# 2_interface.net
KiCad netlist of a schematic drawn in Altium Designer
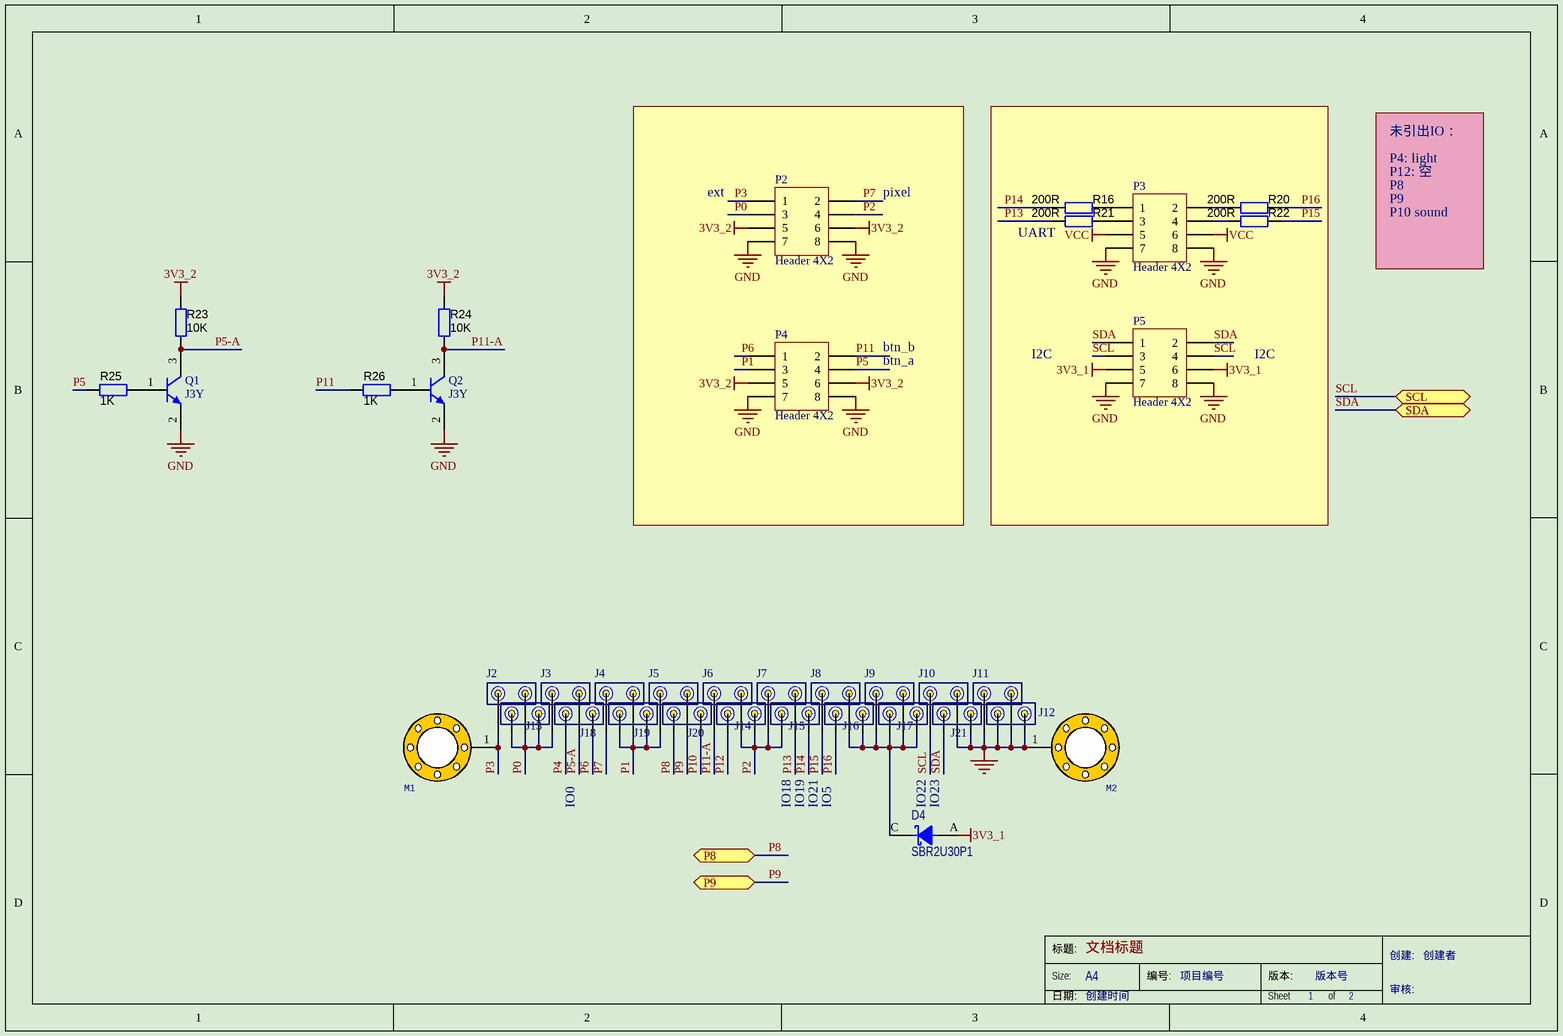
[diagram p0: 2.interface.SchDoc]

(export (version "E")
  (design (tool "Eeschema 10.0.6"))
  (components
    (comp (ref "D4")
      (value "SBR2U30P1")
      (footprint "POWERDI123")
      (fields (field (name "PARTNUMBER") "?") (field (name "PUBLISHER") "Altium Limited"))
      (libsource (lib "03.常用器件") (part "Diode_Schottky"))
    )
    (comp (ref "J2") (value "~") (footprint "顶针座子（2.54MM）") (libsource (lib "Schlib1") (part "pogopin")))
    (comp (ref "J3") (value "~") (footprint "顶针座子（2.54MM）") (libsource (lib "Schlib1") (part "pogopin")))
    (comp (ref "J4") (value "~") (footprint "顶针座子（2.54MM）") (libsource (lib "Schlib1") (part "pogopin")))
    (comp (ref "J5") (value "~") (footprint "顶针座子（2.54MM）") (libsource (lib "Schlib1") (part "pogopin")))
    (comp (ref "J6") (value "~") (footprint "顶针座子（2.54MM）") (libsource (lib "Schlib1") (part "pogopin")))
    (comp (ref "J7") (value "~") (footprint "顶针座子（2.54MM）") (libsource (lib "Schlib1") (part "pogopin")))
    (comp (ref "J8") (value "~") (footprint "顶针座子（2.54MM）") (libsource (lib "Schlib1") (part "pogopin")))
    (comp (ref "J9") (value "~") (footprint "顶针座子（2.54MM）") (libsource (lib "Schlib1") (part "pogopin")))
    (comp (ref "J10") (value "~") (footprint "顶针座子（2.54MM）") (libsource (lib "Schlib1") (part "pogopin")))
    (comp (ref "J11") (value "~") (footprint "顶针座子（2.54MM）") (libsource (lib "Schlib1") (part "pogopin")))
    (comp (ref "J12") (value "~") (footprint "顶针座子（2.54MM）") (libsource (lib "Schlib1") (part "pogopin_32")))
    (comp (ref "J13") (value "~") (footprint "顶针座子（2.54MM）") (libsource (lib "Schlib1") (part "pogopin_32")))
    (comp (ref "J14") (value "~") (footprint "顶针座子（2.54MM）") (libsource (lib "Schlib1") (part "pogopin_32")))
    (comp (ref "J15") (value "~") (footprint "顶针座子（2.54MM）") (libsource (lib "Schlib1") (part "pogopin_32")))
    (comp (ref "J16") (value "~") (footprint "顶针座子（2.54MM）") (libsource (lib "Schlib1") (part "pogopin_32")))
    (comp (ref "J17") (value "~") (footprint "顶针座子（2.54MM）") (libsource (lib "Schlib1") (part "pogopin_32")))
    (comp (ref "J18") (value "~") (footprint "顶针座子（2.54MM）") (libsource (lib "Schlib1") (part "pogopin_32")))
    (comp (ref "J19") (value "~") (footprint "顶针座子（2.54MM）") (libsource (lib "Schlib1") (part "pogopin_32")))
    (comp (ref "J20") (value "~") (footprint "顶针座子（2.54MM）") (libsource (lib "Schlib1") (part "pogopin_32")))
    (comp (ref "J21") (value "~") (footprint "顶针座子（2.54MM）") (libsource (lib "Schlib1") (part "pogopin_32")))
    (comp (ref "M1") (value "~") (footprint "3MM螺丝孔") (libsource (lib "labplus-connector") (part "screw")))
    (comp (ref "M2") (value "~") (footprint "3MM螺丝孔") (libsource (lib "labplus-connector") (part "screw")))
    (comp (ref "P2")
      (value "Header 4X2")
      (footprint "HDR2X4")
      (description "Header, 4-Pin, Dual row")
      (fields (field (name "PUBLISHER") "Altium Limited"))
      (libsource (lib "Miscellaneous Connectors") (part "Header 4X2"))
    )
    (comp (ref "P3")
      (value "Header 4X2")
      (footprint "HDR2X4")
      (description "Header, 4-Pin, Dual row")
      (fields (field (name "PUBLISHER") "Altium Limited"))
      (libsource (lib "Miscellaneous Connectors") (part "Header 4X2"))
    )
    (comp (ref "P4")
      (value "Header 4X2")
      (footprint "HDR2X4")
      (description "Header, 4-Pin, Dual row")
      (fields (field (name "PUBLISHER") "Altium Limited"))
      (libsource (lib "Miscellaneous Connectors") (part "Header 4X2"))
    )
    (comp (ref "P5")
      (value "Header 4X2")
      (footprint "HDR2X4")
      (description "Header, 4-Pin, Dual row")
      (fields (field (name "PUBLISHER") "Altium Limited"))
      (libsource (lib "Miscellaneous Connectors") (part "Header 4X2"))
    )
    (comp (ref "Q1")
      (value "J3Y")
      (footprint "DFN 3L")
      (description "NPN General Purpose Amplifier")
      (fields (field (name "PUBLISHER") "Altium Limited"))
      (libsource (lib "Schlib1") (part "2N3904"))
    )
    (comp (ref "Q2")
      (value "J3Y")
      (footprint "DFN 3L")
      (description "NPN General Purpose Amplifier")
      (fields (field (name "PUBLISHER") "Altium Limited"))
      (libsource (lib "Schlib1") (part "2N3904"))
    )
    (comp (ref "R16")
      (value "200R")
      (footprint "0402")
      (description "RES, 1.0k ohm, 5%, 0.1W, 0603")
      (fields
        (field (name "PARTNUMBER") "RC0603JR-071KL")
        (field (name "MANUFACTURER") "Yageo America")
        (field (name "PUBLISHER") "Texas Instruments")
      )
      (libsource (lib "") (part "RES1_2"))
    )
    (comp (ref "R20")
      (value "200R")
      (footprint "0402")
      (description "RES, 1.0k ohm, 5%, 0.1W, 0603")
      (fields
        (field (name "PARTNUMBER") "RC0603JR-071KL")
        (field (name "MANUFACTURER") "Yageo America")
        (field (name "PUBLISHER") "Texas Instruments")
      )
      (libsource (lib "") (part "RES1_2"))
    )
    (comp (ref "R21")
      (value "200R")
      (footprint "0402")
      (description "RES, 1.0k ohm, 5%, 0.1W, 0603")
      (fields
        (field (name "PARTNUMBER") "RC0603JR-071KL")
        (field (name "MANUFACTURER") "Yageo America")
        (field (name "PUBLISHER") "Texas Instruments")
      )
      (libsource (lib "") (part "RES1_2"))
    )
    (comp (ref "R22")
      (value "200R")
      (footprint "0402")
      (description "RES, 1.0k ohm, 5%, 0.1W, 0603")
      (fields
        (field (name "PARTNUMBER") "RC0603JR-071KL")
        (field (name "MANUFACTURER") "Yageo America")
        (field (name "PUBLISHER") "Texas Instruments")
      )
      (libsource (lib "") (part "RES1_2"))
    )
    (comp (ref "R23")
      (value "10K")
      (footprint "0402")
      (description "RES, 1.0k ohm, 5%, 0.1W, 0603")
      (fields
        (field (name "PARTNUMBER") "RC0603JR-071KL")
        (field (name "MANUFACTURER") "Yageo America")
        (field (name "PUBLISHER") "Texas Instruments")
      )
      (libsource (lib "03.常用器件") (part "RES1"))
    )
    (comp (ref "R24")
      (value "10K")
      (footprint "0402")
      (description "RES, 1.0k ohm, 5%, 0.1W, 0603")
      (fields
        (field (name "PARTNUMBER") "RC0603JR-071KL")
        (field (name "MANUFACTURER") "Yageo America")
        (field (name "PUBLISHER") "Texas Instruments")
      )
      (libsource (lib "03.常用器件") (part "RES1"))
    )
    (comp (ref "R25")
      (value "1K")
      (footprint "0402")
      (description "RES, 1.0k ohm, 5%, 0.1W, 0603")
      (fields
        (field (name "PARTNUMBER") "RC0603JR-071KL")
        (field (name "MANUFACTURER") "Yageo America")
        (field (name "PUBLISHER") "Texas Instruments")
      )
      (libsource (lib "") (part "RES1_1"))
    )
    (comp (ref "R26")
      (value "1K")
      (footprint "0402")
      (description "RES, 1.0k ohm, 5%, 0.1W, 0603")
      (fields
        (field (name "PARTNUMBER") "RC0603JR-071KL")
        (field (name "MANUFACTURER") "Yageo America")
        (field (name "PUBLISHER") "Texas Instruments")
      )
      (libsource (lib "") (part "RES1_1"))
    )
  )
  (nets
    (net (code "1") (name "/P0") (class "Default")
      (node (ref "J13") (pin "1") (pinfunction "1_1") (pintype "passive"))
      (node (ref "J13") (pin "2") (pinfunction "2_2") (pintype "passive"))
      (node (ref "J2") (pin "2") (pinfunction "2_2") (pintype "passive"))
      (node (ref "J3") (pin "1") (pinfunction "1_1") (pintype "passive"))
      (node (ref "P2") (pin "3") (pinfunction "3_3") (pintype "passive"))
    )
    (net (code "2") (name "/P1") (class "Default")
      (node (ref "J19") (pin "1") (pinfunction "1_1") (pintype "passive"))
      (node (ref "J19") (pin "2") (pinfunction "2_2") (pintype "passive"))
      (node (ref "J4") (pin "2") (pinfunction "2_2") (pintype "passive"))
      (node (ref "J5") (pin "1") (pinfunction "1_1") (pintype "passive"))
      (node (ref "P4") (pin "3") (pinfunction "3_3") (pintype "passive"))
    )
    (net (code "3") (name "/P2") (class "Default")
      (node (ref "J14") (pin "2") (pinfunction "2_2") (pintype "passive"))
      (node (ref "J15") (pin "1") (pinfunction "1_1") (pintype "passive"))
      (node (ref "J6") (pin "2") (pinfunction "2_2") (pintype "passive"))
      (node (ref "J7") (pin "1") (pinfunction "1_1") (pintype "passive"))
      (node (ref "P2") (pin "4") (pinfunction "4_4") (pintype "passive"))
    )
    (net (code "4") (name "/P3") (class "Default")
      (node (ref "J2") (pin "1") (pinfunction "1_1") (pintype "passive"))
      (node (ref "M1") (pin "1") (pinfunction "1_1") (pintype "passive"))
      (node (ref "P2") (pin "1") (pinfunction "1_1") (pintype "passive"))
    )
    (net (code "5") (name "/P4") (class "Default")
      (node (ref "J18") (pin "1") (pinfunction "1_1") (pintype "passive"))
    )
    (net (code "6") (name "/P5") (class "Default")
      (node (ref "P4") (pin "4") (pinfunction "4_4") (pintype "passive"))
      (node (ref "R25") (pin "1") (pinfunction "1_1") (pintype "passive"))
    )
    (net (code "7") (name "/P5-A") (class "Default")
      (node (ref "J3") (pin "2") (pinfunction "2_2") (pintype "passive"))
      (node (ref "Q1") (pin "3") (pinfunction "C_3") (pintype "passive"))
      (node (ref "R23") (pin "2") (pinfunction "2_2") (pintype "passive"))
    )
    (net (code "8") (name "/P6") (class "Default")
      (node (ref "J18") (pin "2") (pinfunction "2_2") (pintype "passive"))
      (node (ref "P4") (pin "1") (pinfunction "1_1") (pintype "passive"))
    )
    (net (code "9") (name "/P7") (class "Default")
      (node (ref "J4") (pin "1") (pinfunction "1_1") (pintype "passive"))
      (node (ref "P2") (pin "2") (pinfunction "2_2") (pintype "passive"))
    )
    (net (code "10") (name "/P8") (class "Default")
      (node (ref "J20") (pin "1") (pinfunction "1_1") (pintype "passive"))
    )
    (net (code "11") (name "/P9") (class "Default")
      (node (ref "J5") (pin "2") (pinfunction "2_2") (pintype "passive"))
    )
    (net (code "12") (name "/P10") (class "Default")
      (node (ref "J20") (pin "2") (pinfunction "2_2") (pintype "passive"))
    )
    (net (code "13") (name "/P11") (class "Default")
      (node (ref "P4") (pin "2") (pinfunction "2_2") (pintype "passive"))
      (node (ref "R26") (pin "1") (pinfunction "1_1") (pintype "passive"))
    )
    (net (code "14") (name "/P11-A") (class "Default")
      (node (ref "J6") (pin "1") (pinfunction "1_1") (pintype "passive"))
      (node (ref "Q2") (pin "3") (pinfunction "C_3") (pintype "passive"))
      (node (ref "R24") (pin "2") (pinfunction "2_2") (pintype "passive"))
    )
    (net (code "15") (name "/P12") (class "Default")
      (node (ref "J14") (pin "1") (pinfunction "1_1") (pintype "passive"))
    )
    (net (code "16") (name "/P13") (class "Default")
      (node (ref "J7") (pin "2") (pinfunction "2_2") (pintype "passive"))
      (node (ref "R21") (pin "1") (pinfunction "1_1") (pintype "passive"))
    )
    (net (code "17") (name "/P14") (class "Default")
      (node (ref "J15") (pin "2") (pinfunction "2_2") (pintype "passive"))
      (node (ref "R16") (pin "1") (pinfunction "1_1") (pintype "passive"))
    )
    (net (code "18") (name "/P15") (class "Default")
      (node (ref "J8") (pin "1") (pinfunction "1_1") (pintype "passive"))
      (node (ref "R22") (pin "2") (pinfunction "2_2") (pintype "passive"))
    )
    (net (code "19") (name "/P16") (class "Default")
      (node (ref "J16") (pin "1") (pinfunction "1_1") (pintype "passive"))
      (node (ref "R20") (pin "2") (pinfunction "2_2") (pintype "passive"))
    )
    (net (code "20") (name "/SCL") (class "Default")
      (node (ref "J10") (pin "1") (pinfunction "1_1") (pintype "passive"))
      (node (ref "P5") (pin "3") (pinfunction "3_3") (pintype "passive"))
      (node (ref "P5") (pin "4") (pinfunction "4_4") (pintype "passive"))
    )
    (net (code "21") (name "/SDA") (class "Default")
      (node (ref "J21") (pin "1") (pinfunction "1_1") (pintype "passive"))
      (node (ref "P5") (pin "1") (pinfunction "1_1") (pintype "passive"))
      (node (ref "P5") (pin "2") (pinfunction "2_2") (pintype "passive"))
    )
    (net (code "22") (name "3V3_1") (class "Default")
      (node (ref "D4") (pin "A") (pinfunction "ANODE_A") (pintype "passive"))
      (node (ref "P5") (pin "5") (pinfunction "5_5") (pintype "passive"))
      (node (ref "P5") (pin "6") (pinfunction "6_6") (pintype "passive"))
    )
    (net (code "23") (name "3V3_2") (class "Default")
      (node (ref "P2") (pin "5") (pinfunction "5_5") (pintype "passive"))
      (node (ref "P2") (pin "6") (pinfunction "6_6") (pintype "passive"))
      (node (ref "P4") (pin "5") (pinfunction "5_5") (pintype "passive"))
      (node (ref "P4") (pin "6") (pinfunction "6_6") (pintype "passive"))
      (node (ref "R23") (pin "1") (pinfunction "1_1") (pintype "passive"))
      (node (ref "R24") (pin "1") (pinfunction "1_1") (pintype "passive"))
    )
    (net (code "24") (name "GND") (class "Default")
      (node (ref "J10") (pin "2") (pinfunction "2_2") (pintype "passive"))
      (node (ref "J11") (pin "1") (pinfunction "1_1") (pintype "passive"))
      (node (ref "J11") (pin "2") (pinfunction "2_2") (pintype "passive"))
      (node (ref "J12") (pin "1") (pinfunction "1_1") (pintype "passive"))
      (node (ref "J12") (pin "2") (pinfunction "2_2") (pintype "passive"))
      (node (ref "J21") (pin "2") (pinfunction "2_2") (pintype "passive"))
      (node (ref "M2") (pin "1") (pinfunction "1_1") (pintype "passive"))
      (node (ref "P2") (pin "7") (pinfunction "7_7") (pintype "passive"))
      (node (ref "P2") (pin "8") (pinfunction "8_8") (pintype "passive"))
      (node (ref "P3") (pin "7") (pinfunction "7_7") (pintype "passive"))
      (node (ref "P3") (pin "8") (pinfunction "8_8") (pintype "passive"))
      (node (ref "P4") (pin "7") (pinfunction "7_7") (pintype "passive"))
      (node (ref "P4") (pin "8") (pinfunction "8_8") (pintype "passive"))
      (node (ref "P5") (pin "7") (pinfunction "7_7") (pintype "passive"))
      (node (ref "P5") (pin "8") (pinfunction "8_8") (pintype "passive"))
      (node (ref "Q1") (pin "2") (pinfunction "E_2") (pintype "passive"))
      (node (ref "Q2") (pin "2") (pinfunction "E_2") (pintype "passive"))
    )
    (net (code "25") (name "Net-(D4-CATHODE)") (class "Default")
      (node (ref "D4") (pin "C") (pinfunction "CATHODE_C") (pintype "passive"))
      (node (ref "J16") (pin "2") (pinfunction "2_2") (pintype "passive"))
      (node (ref "J17") (pin "1") (pinfunction "1_1") (pintype "passive"))
      (node (ref "J17") (pin "2") (pinfunction "2_2") (pintype "passive"))
      (node (ref "J8") (pin "2") (pinfunction "2_2") (pintype "passive"))
      (node (ref "J9") (pin "1") (pinfunction "1_1") (pintype "passive"))
      (node (ref "J9") (pin "2") (pinfunction "2_2") (pintype "passive"))
    )
    (net (code "26") (name "Net-(P3-Pad1)") (class "Default")
      (node (ref "P3") (pin "1") (pinfunction "1_1") (pintype "passive"))
      (node (ref "R16") (pin "2") (pinfunction "2_2") (pintype "passive"))
    )
    (net (code "27") (name "Net-(P3-Pad2)") (class "Default")
      (node (ref "P3") (pin "2") (pinfunction "2_2") (pintype "passive"))
      (node (ref "R20") (pin "1") (pinfunction "1_1") (pintype "passive"))
    )
    (net (code "28") (name "Net-(P3-Pad3)") (class "Default")
      (node (ref "P3") (pin "3") (pinfunction "3_3") (pintype "passive"))
      (node (ref "R21") (pin "2") (pinfunction "2_2") (pintype "passive"))
    )
    (net (code "29") (name "Net-(P3-Pad4)") (class "Default")
      (node (ref "P3") (pin "4") (pinfunction "4_4") (pintype "passive"))
      (node (ref "R22") (pin "1") (pinfunction "1_1") (pintype "passive"))
    )
    (net (code "30") (name "Net-(Q1-B)") (class "Default")
      (node (ref "Q1") (pin "1") (pinfunction "B_1") (pintype "passive"))
      (node (ref "R25") (pin "2") (pinfunction "2_2") (pintype "passive"))
    )
    (net (code "31") (name "Net-(Q2-B)") (class "Default")
      (node (ref "Q2") (pin "1") (pinfunction "B_1") (pintype "passive"))
      (node (ref "R26") (pin "2") (pinfunction "2_2") (pintype "passive"))
    )
    (net (code "32") (name "VCC") (class "Default")
      (node (ref "P3") (pin "5") (pinfunction "5_5") (pintype "passive"))
      (node (ref "P3") (pin "6") (pinfunction "6_6") (pintype "passive"))
    )
  )
)
